# Discharge_Board_rev2.net
KiCad netlist of a schematic drawn in EAGLE
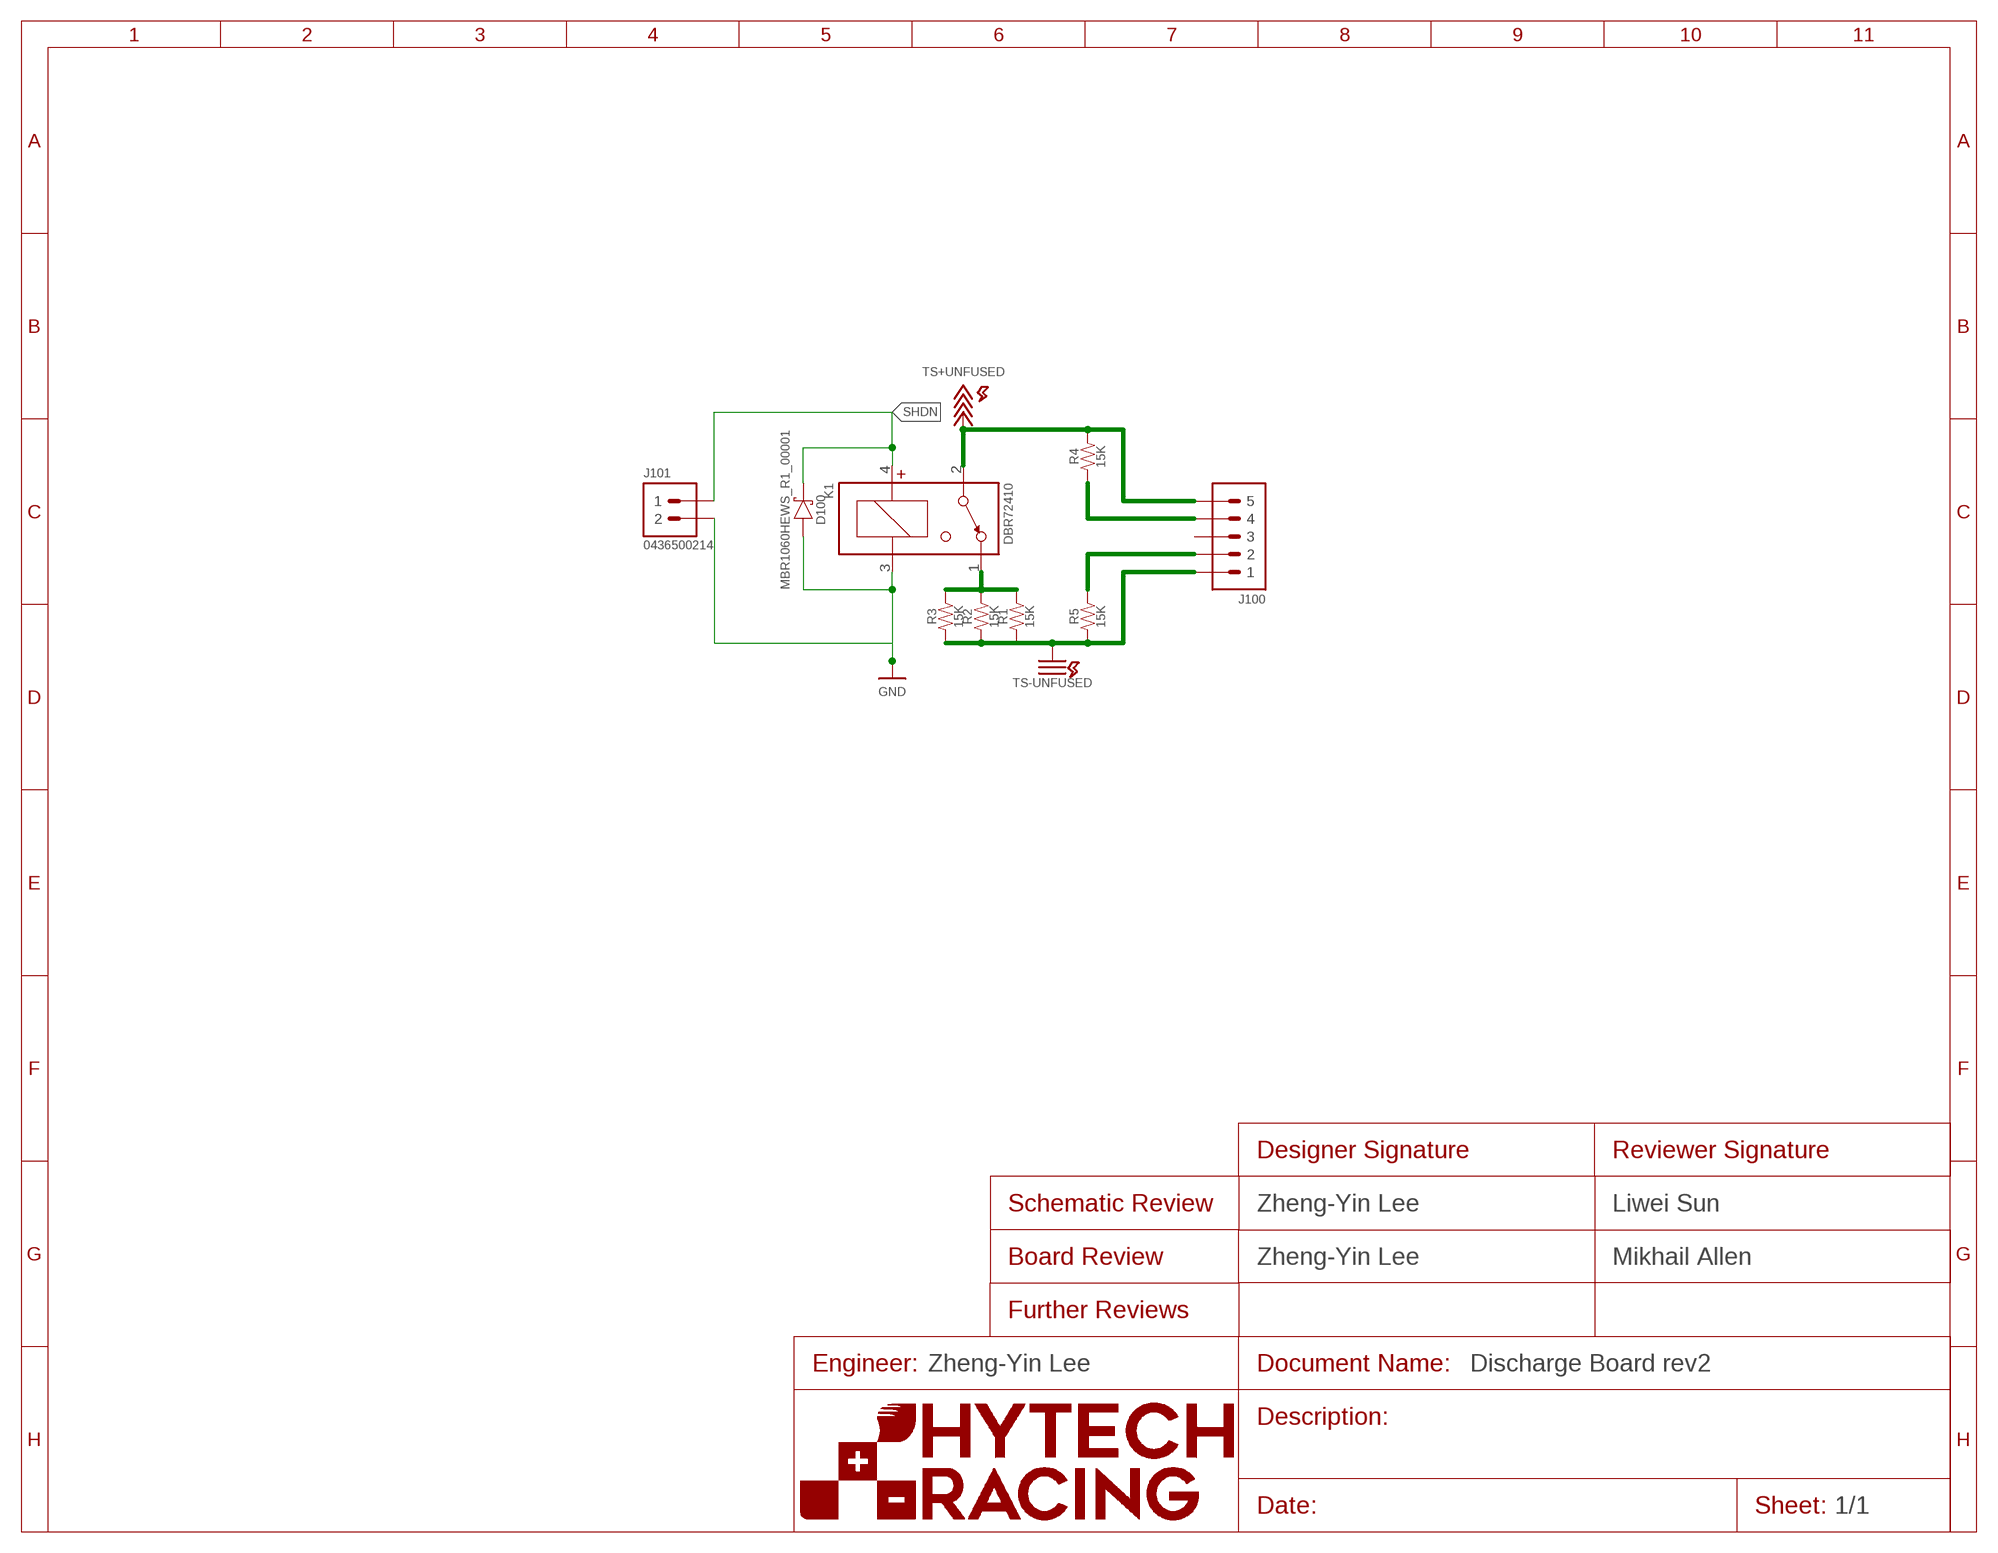
[diagram p0: schematic, sheet 1]

(export (version "E")
  (design (tool "Eeschema 10.0.6"))
  (components
    (comp (ref "D100")
      (value "SCHOTTKY_SOD323_60V")
      (footprint "eagle-import:SOD-323")
      (fields
        (field (name "MANUFACTURER") "Panjit International Inc.")
        (field (name "MPN") "MBR1060HEWS_R1_00001")
        (field (name "VOLTAGE") "60V")
      )
      (libsource (lib "eagle-import") (part "SCHOTTKY_?_SOD32360V"))
    )
    (comp (ref "J100")
      (value "CONNECTOR-5_MICRO_R5S_")
      (footprint "eagle-import:MOLEX_MICROFIT_SMD_RIGHTANGLE_05_SINGLE")
      (libsource (lib "eagle-import") (part "CONNECTOR-5_?_MICRO_R5S"))
    )
    (comp (ref "J101")
      (value "CONNECTOR-2_MICROFIT_SMD_RIGHTANGLE_02_SINGLE_BLACK")
      (footprint "eagle-import:MOLEX_MICROFIT_SMD_RIGHTANGLE_02_SINGLE")
      (fields (field (name "MANUFACTURER") "Molex") (field (name "MPN") "0436500214"))
      (libsource (lib "eagle-import") (part "CONNECTOR-2_?_MICROFIT_SMD_RIGHTANGLE_02_SINGLEBLACK"))
    )
    (comp (ref "K1")
      (value "RELAY_SPST_NC_POLARIZED_D_24")
      (footprint "eagle-import:D")
      (fields (field (name "MANUFACTURER") "Sensata-Cynergy3") (field (name "MPN") "DBR72410"))
      (libsource (lib "eagle-import") (part "RELAY_SPST_NC_POLARIZED_?D_24"))
    )
    (comp (ref "R1")
      (value "RESISTOR_B20-SHORTENED_15K")
      (footprint "eagle-import:B20-SHORTENED")
      (fields
        (field (name "MANUFACTURER") "Ohmite")
        (field (name "MPN") "B20J15KE")
        (field (name "POWER") "20W")
        (field (name "RESISTANCE") "15K")
      )
      (libsource (lib "eagle-import") (part "RESISTOR_?_B20-SHORTENED15K"))
    )
    (comp (ref "R2")
      (value "RESISTOR_B20-SHORTENED_15K")
      (footprint "eagle-import:B20-SHORTENED")
      (fields
        (field (name "MANUFACTURER") "Ohmite")
        (field (name "MPN") "B20J15KE")
        (field (name "POWER") "20W")
        (field (name "RESISTANCE") "15K")
      )
      (libsource (lib "eagle-import") (part "RESISTOR_?_B20-SHORTENED15K"))
    )
    (comp (ref "R3")
      (value "RESISTOR_B20-SHORTENED_15K")
      (footprint "eagle-import:B20-SHORTENED")
      (fields
        (field (name "MANUFACTURER") "Ohmite")
        (field (name "MPN") "B20J15KE")
        (field (name "POWER") "20W")
        (field (name "RESISTANCE") "15K")
      )
      (libsource (lib "eagle-import") (part "RESISTOR_?_B20-SHORTENED15K"))
    )
    (comp (ref "R4")
      (value "RESISTOR_B20-SHORTENED_15K")
      (footprint "eagle-import:B20-SHORTENED")
      (fields
        (field (name "MANUFACTURER") "Ohmite")
        (field (name "MPN") "B20J15KE")
        (field (name "POWER") "20W")
        (field (name "RESISTANCE") "15K")
      )
      (libsource (lib "eagle-import") (part "RESISTOR_?_B20-SHORTENED15K"))
    )
    (comp (ref "R5")
      (value "RESISTOR_B20-SHORTENED_15K")
      (footprint "eagle-import:B20-SHORTENED")
      (fields
        (field (name "MANUFACTURER") "Ohmite")
        (field (name "MPN") "B20J15KE")
        (field (name "POWER") "20W")
        (field (name "RESISTANCE") "15K")
      )
      (libsource (lib "eagle-import") (part "RESISTOR_?_B20-SHORTENED15K"))
    )
  )
  (nets
    (net (code "1") (name "GND") (class "Default")
      (node (ref "D100") (pin "A") (pinfunction "A_A") (pintype "passive"))
      (node (ref "J101") (pin "2") (pinfunction "2_2") (pintype "passive"))
      (node (ref "K1") (pin "3") (pinfunction "COIL-_3") (pintype "bidirectional"))
    )
    (net (code "2") (name "Net-(J100-Pad2)") (class "Default")
      (node (ref "J100") (pin "2") (pinfunction "2_2") (pintype "passive"))
      (node (ref "R5") (pin "2") (pinfunction "2_2") (pintype "passive"))
    )
    (net (code "3") (name "Net-(J100-Pad4)") (class "Default")
      (node (ref "J100") (pin "4") (pinfunction "4_4") (pintype "passive"))
      (node (ref "R4") (pin "1") (pinfunction "1_1") (pintype "passive"))
    )
    (net (code "4") (name "Net-(K1-CONTACT2)") (class "Default")
      (node (ref "K1") (pin "1") (pinfunction "CONTACT2_1") (pintype "bidirectional"))
      (node (ref "R1") (pin "2") (pinfunction "2_2") (pintype "passive"))
      (node (ref "R2") (pin "2") (pinfunction "2_2") (pintype "passive"))
      (node (ref "R3") (pin "2") (pinfunction "2_2") (pintype "passive"))
    )
    (net (code "5") (name "SHDN") (class "Default")
      (node (ref "D100") (pin "C") (pinfunction "C_C") (pintype "passive"))
      (node (ref "J101") (pin "1") (pinfunction "1_1") (pintype "passive"))
      (node (ref "K1") (pin "4") (pinfunction "COIL+_4") (pintype "bidirectional"))
    )
    (net (code "6") (name "TS+UNFUSED") (class "Default")
      (node (ref "J100") (pin "5") (pinfunction "5_5") (pintype "passive"))
      (node (ref "K1") (pin "2") (pinfunction "CONTACT1_2") (pintype "bidirectional"))
      (node (ref "R4") (pin "2") (pinfunction "2_2") (pintype "passive"))
    )
    (net (code "7") (name "TS-UNFUSED") (class "Default")
      (node (ref "J100") (pin "1") (pinfunction "1_1") (pintype "passive"))
      (node (ref "R1") (pin "1") (pinfunction "1_1") (pintype "passive"))
      (node (ref "R2") (pin "1") (pinfunction "1_1") (pintype "passive"))
      (node (ref "R3") (pin "1") (pinfunction "1_1") (pintype "passive"))
      (node (ref "R5") (pin "1") (pinfunction "1_1") (pintype "passive"))
    )
    (net (code "8") (name "unconnected-(J100-Pad3)") (class "Default")
      (node (ref "J100") (pin "3") (pinfunction "3_3") (pintype "passive"))
    )
  )
)
